# 1_3.net
KiCad netlist of a schematic drawn in Altium Designer
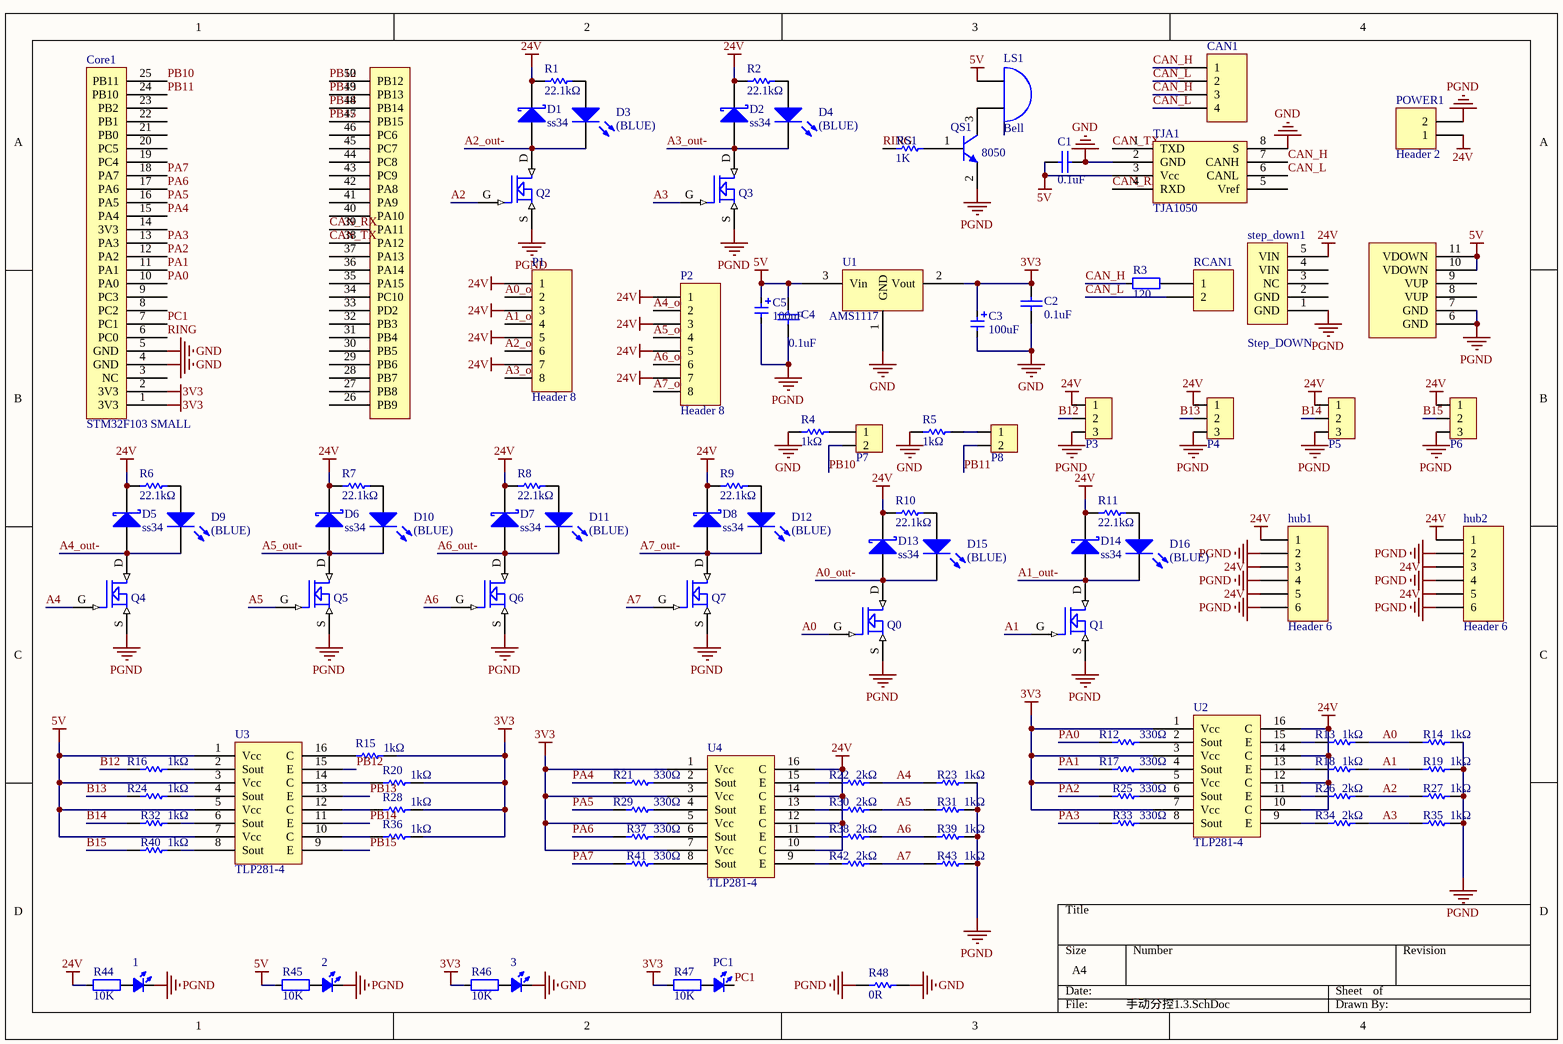
[diagram p0: 手动分控1.3.SchDoc]

(export (version "E")
  (design (tool "Eeschema 10.0.6"))
  (components
    (comp (ref "1")
      (value "LED_0603")
      (footprint "LED_0805_GREEN")
      (description "LED")
      (libsource (lib "Integrated_Library") (part "LED_0603"))
    )
    (comp (ref "2")
      (value "LED_0603")
      (footprint "LED_0805_GREEN")
      (description "LED")
      (libsource (lib "Integrated_Library") (part "LED_0603"))
    )
    (comp (ref "3")
      (value "LED_0603")
      (footprint "LED_0805_GREEN")
      (description "LED")
      (libsource (lib "Integrated_Library") (part "LED_0603"))
    )
    (comp (ref "C1")
      (value "0.1uF")
      (footprint "CAP-MLCC-0603")
      (description "Capacitor")
      (fields (field (name "Comment") "Cap") (field (name "PUBLISHER") "Altium Limited"))
      (libsource (lib "K60-mainboard-v3.1") (part "Cap"))
    )
    (comp (ref "C2")
      (value "0.1uF")
      (footprint "CAP-MLCC-0603")
      (description "Capacitor")
      (fields (field (name "Comment") "Cap") (field (name "PUBLISHER") "Altium Limited"))
      (libsource (lib "K60-mainboard-v3.1") (part "Cap"))
    )
    (comp (ref "C3")
      (value "100uF")
      (footprint "CAP-TAN-7343/CAPD")
      (description "Capacitor")
      (fields (field (name "Comment") "Cap_Tan_0805"))
      (libsource (lib "Integrated_Library") (part "Cap_Tan_0805"))
    )
    (comp (ref "C4")
      (value "0.1uF")
      (footprint "CAP-MLCC-0603")
      (description "Capacitor")
      (fields (field (name "Comment") "Cap") (field (name "PUBLISHER") "Altium Limited"))
      (libsource (lib "K60-mainboard-v3.1") (part "Cap"))
    )
    (comp (ref "C5")
      (value "100uF")
      (footprint "CAP-TAN-7343/CAPD")
      (description "Capacitor")
      (fields (field (name "Comment") "Cap_Tan_0805"))
      (libsource (lib "Integrated_Library") (part "Cap_Tan_0805"))
    )
    (comp (ref "CAN1")
      (value "Header 4")
      (footprint "Green_4P")
      (description "Header, 4-Pin")
      (fields (field (name "PUBLISHER") "Altium Limited"))
      (libsource (lib "Libraries_2014_0618") (part "Header 4"))
    )
    (comp (ref "Core1")
      (value "STM32F103 SMALL")
      (footprint "STM32F103Small")
      (libsource (lib "K60-mainboard-v3.1") (part "STM32F103 SMALL"))
    )
    (comp (ref "D1")
      (value "ss34")
      (footprint "ss34")
      (description "肖特基二极管")
      (fields (field (name "PUBLISHER") "Altium Limited"))
      (libsource (lib "Libraries_2014_0618") (part "DIODE-Schottky"))
    )
    (comp (ref "D2")
      (value "ss34")
      (footprint "ss34")
      (description "肖特基二极管")
      (fields (field (name "PUBLISHER") "Altium Limited"))
      (libsource (lib "Libraries_2014_0618") (part "DIODE-Schottky"))
    )
    (comp (ref "D3")
      (value "(BLUE)")
      (footprint "LED-0805")
      (description "LED")
      (fields (field (name "PUBLISHER") "Altium Limited"))
      (libsource (lib "Libraries_2014_0618") (part "LED"))
    )
    (comp (ref "D4")
      (value "(BLUE)")
      (footprint "LED-0805")
      (description "LED")
      (fields (field (name "PUBLISHER") "Altium Limited"))
      (libsource (lib "Libraries_2014_0618") (part "LED"))
    )
    (comp (ref "D5")
      (value "ss34")
      (footprint "ss34")
      (description "肖特基二极管")
      (fields (field (name "PUBLISHER") "Altium Limited"))
      (libsource (lib "Libraries_2014_0618") (part "DIODE-Schottky"))
    )
    (comp (ref "D6")
      (value "ss34")
      (footprint "ss34")
      (description "肖特基二极管")
      (fields (field (name "PUBLISHER") "Altium Limited"))
      (libsource (lib "Libraries_2014_0618") (part "DIODE-Schottky"))
    )
    (comp (ref "D7")
      (value "ss34")
      (footprint "ss34")
      (description "肖特基二极管")
      (fields (field (name "PUBLISHER") "Altium Limited"))
      (libsource (lib "Libraries_2014_0618") (part "DIODE-Schottky"))
    )
    (comp (ref "D8")
      (value "ss34")
      (footprint "ss34")
      (description "肖特基二极管")
      (fields (field (name "PUBLISHER") "Altium Limited"))
      (libsource (lib "Libraries_2014_0618") (part "DIODE-Schottky"))
    )
    (comp (ref "D9")
      (value "(BLUE)")
      (footprint "LED-0805")
      (description "LED")
      (fields (field (name "PUBLISHER") "Altium Limited"))
      (libsource (lib "Libraries_2014_0618") (part "LED"))
    )
    (comp (ref "D10")
      (value "(BLUE)")
      (footprint "LED-0805")
      (description "LED")
      (fields (field (name "PUBLISHER") "Altium Limited"))
      (libsource (lib "Libraries_2014_0618") (part "LED"))
    )
    (comp (ref "D11")
      (value "(BLUE)")
      (footprint "LED-0805")
      (description "LED")
      (fields (field (name "PUBLISHER") "Altium Limited"))
      (libsource (lib "Libraries_2014_0618") (part "LED"))
    )
    (comp (ref "D12")
      (value "(BLUE)")
      (footprint "LED-0805")
      (description "LED")
      (fields (field (name "PUBLISHER") "Altium Limited"))
      (libsource (lib "Libraries_2014_0618") (part "LED"))
    )
    (comp (ref "D13")
      (value "ss34")
      (footprint "ss34")
      (description "肖特基二极管")
      (fields (field (name "PUBLISHER") "Altium Limited"))
      (libsource (lib "Libraries_2014_0618") (part "DIODE-Schottky"))
    )
    (comp (ref "D14")
      (value "ss34")
      (footprint "ss34")
      (description "肖特基二极管")
      (fields (field (name "PUBLISHER") "Altium Limited"))
      (libsource (lib "Libraries_2014_0618") (part "DIODE-Schottky"))
    )
    (comp (ref "D15")
      (value "(BLUE)")
      (footprint "LED-0805")
      (description "LED")
      (fields (field (name "PUBLISHER") "Altium Limited"))
      (libsource (lib "Libraries_2014_0618") (part "LED"))
    )
    (comp (ref "D16")
      (value "(BLUE)")
      (footprint "LED-0805")
      (description "LED")
      (fields (field (name "PUBLISHER") "Altium Limited"))
      (libsource (lib "Libraries_2014_0618") (part "LED"))
    )
    (comp (ref "hub1")
      (value "Header 6")
      (footprint "Green_6P")
      (description "Header, 6-Pin")
      (fields (field (name "PUBLISHER") "Altium Limited"))
      (libsource (lib "Libraries_2014_0618") (part "Header 6"))
    )
    (comp (ref "hub2")
      (value "Header 6")
      (footprint "Green_6P")
      (description "Header, 6-Pin")
      (fields (field (name "PUBLISHER") "Altium Limited"))
      (libsource (lib "Libraries_2014_0618") (part "Header 6"))
    )
    (comp (ref "LS1")
      (value "Bell")
      (footprint "CAP-ELE-PIN200/DIA250")
      (description "Electrical Bell")
      (fields (field (name "PUBLISHER") "Altium Limited"))
      (libsource (lib "Miscellaneous Devices") (part "Bell"))
    )
    (comp (ref "P1")
      (value "Header 8")
      (footprint "Green_8P")
      (description "Header, 8-Pin")
      (fields (field (name "PUBLISHER") "Altium Limited"))
      (libsource (lib "K60-mainboard-v3.1") (part "Header 8"))
    )
    (comp (ref "P2")
      (value "Header 8")
      (footprint "Green_8P")
      (description "Header, 8-Pin")
      (fields (field (name "PUBLISHER") "Altium Limited"))
      (libsource (lib "K60-mainboard-v3.1") (part "Header 8"))
    )
    (comp (ref "P3")
      (value "HDR1x3_2.54")
      (footprint "Green_3P")
      (description "Header")
      (libsource (lib "Integrated_Library") (part "HDR1x3_2.54"))
    )
    (comp (ref "P4")
      (value "HDR1x3_2.54")
      (footprint "Green_3P")
      (description "Header")
      (libsource (lib "Integrated_Library") (part "HDR1x3_2.54"))
    )
    (comp (ref "P5")
      (value "HDR1x3_2.54")
      (footprint "Green_3P")
      (description "Header")
      (libsource (lib "Integrated_Library") (part "HDR1x3_2.54"))
    )
    (comp (ref "P6")
      (value "HDR1x3_2.54")
      (footprint "Green_3P")
      (description "Header")
      (libsource (lib "Integrated_Library") (part "HDR1x3_2.54"))
    )
    (comp (ref "P7")
      (value "HDR1x2_2.54")
      (footprint "Green_2P")
      (description "Header")
      (libsource (lib "Integrated_Library") (part "HDR1x2_2.54"))
    )
    (comp (ref "P8")
      (value "HDR1x2_2.54")
      (footprint "Green_2P")
      (description "Header")
      (libsource (lib "Integrated_Library") (part "HDR1x2_2.54"))
    )
    (comp (ref "PC1")
      (value "LED_0603")
      (footprint "LED_0805_GREEN")
      (description "LED")
      (libsource (lib "Integrated_Library") (part "LED_0603"))
    )
    (comp (ref "POWER1")
      (value "Header 2")
      (footprint "Green_2P")
      (description "Header, 2-Pin")
      (fields (field (name "PUBLISHER") "Altium Limited"))
      (libsource (lib "K60-mainboard-v3.1") (part "Header 2"))
    )
    (comp (ref "Q0")
      (value "MOSFET N")
      (footprint "LR7843")
      (description "IRF530")
      (libsource (lib "K60-mainboard-v3.1") (part "MOSFET N"))
    )
    (comp (ref "Q1")
      (value "MOSFET N")
      (footprint "LR7843")
      (description "IRF530")
      (libsource (lib "K60-mainboard-v3.1") (part "MOSFET N"))
    )
    (comp (ref "Q2")
      (value "MOSFET N")
      (footprint "NMOS_SOT23")
      (description "IRF530")
      (libsource (lib "K60-mainboard-v3.1") (part "MOSFET N"))
    )
    (comp (ref "Q3")
      (value "MOSFET N")
      (footprint "NMOS_SOT23")
      (description "IRF530")
      (libsource (lib "K60-mainboard-v3.1") (part "MOSFET N"))
    )
    (comp (ref "Q4")
      (value "MOSFET N")
      (footprint "NMOS_SOT23")
      (description "IRF530")
      (libsource (lib "K60-mainboard-v3.1") (part "MOSFET N"))
    )
    (comp (ref "Q5")
      (value "MOSFET N")
      (footprint "NMOS_SOT23")
      (description "IRF530")
      (libsource (lib "K60-mainboard-v3.1") (part "MOSFET N"))
    )
    (comp (ref "Q6")
      (value "MOSFET N")
      (footprint "NMOS_SOT23")
      (description "IRF530")
      (libsource (lib "K60-mainboard-v3.1") (part "MOSFET N"))
    )
    (comp (ref "Q7")
      (value "MOSFET N")
      (footprint "NMOS_SOT23")
      (description "IRF530")
      (libsource (lib "K60-mainboard-v3.1") (part "MOSFET N"))
    )
    (comp (ref "QS1")
      (value "8050")
      (footprint "SOT-23B_N")
      (description "NPN Bipolar Transistor")
      (fields (field (name "PUBLISHER") "Altium Limited"))
      (libsource (lib "附加元件") (part "QNPN"))
    )
    (comp (ref "R1")
      (value "22.1kΩ")
      (footprint "RES-0603")
      (description "电阻")
      (fields (field (name "PUBLISHER") "Altium Limited"))
      (libsource (lib "Libraries_2014_0618") (part "RES"))
    )
    (comp (ref "R2")
      (value "22.1kΩ")
      (footprint "RES-0603")
      (description "电阻")
      (fields (field (name "PUBLISHER") "Altium Limited"))
      (libsource (lib "Libraries_2014_0618") (part "RES"))
    )
    (comp (ref "R3")
      (value "120")
      (footprint "RES-0603")
      (description "Resistor")
      (fields (field (name "Comment") "Res_0603"))
      (libsource (lib "Integrated_Library") (part "Res_0603"))
    )
    (comp (ref "R4")
      (value "1kΩ")
      (footprint "RES-0603")
      (description "电阻")
      (fields (field (name "PUBLISHER") "Altium Limited"))
      (libsource (lib "Libraries_2014_0618") (part "RES"))
    )
    (comp (ref "R5")
      (value "1kΩ")
      (footprint "RES-0603")
      (description "电阻")
      (fields (field (name "PUBLISHER") "Altium Limited"))
      (libsource (lib "Libraries_2014_0618") (part "RES"))
    )
    (comp (ref "R6")
      (value "22.1kΩ")
      (footprint "RES-0603")
      (description "电阻")
      (fields (field (name "PUBLISHER") "Altium Limited"))
      (libsource (lib "Libraries_2014_0618") (part "RES"))
    )
    (comp (ref "R7")
      (value "22.1kΩ")
      (footprint "RES-0603")
      (description "电阻")
      (fields (field (name "PUBLISHER") "Altium Limited"))
      (libsource (lib "Libraries_2014_0618") (part "RES"))
    )
    (comp (ref "R8")
      (value "22.1kΩ")
      (footprint "RES-0603")
      (description "电阻")
      (fields (field (name "PUBLISHER") "Altium Limited"))
      (libsource (lib "Libraries_2014_0618") (part "RES"))
    )
    (comp (ref "R9")
      (value "22.1kΩ")
      (footprint "RES-0603")
      (description "电阻")
      (fields (field (name "PUBLISHER") "Altium Limited"))
      (libsource (lib "Libraries_2014_0618") (part "RES"))
    )
    (comp (ref "R10")
      (value "22.1kΩ")
      (footprint "RES-0603")
      (description "电阻")
      (fields (field (name "PUBLISHER") "Altium Limited"))
      (libsource (lib "Libraries_2014_0618") (part "RES"))
    )
    (comp (ref "R11")
      (value "22.1kΩ")
      (footprint "RES-0603")
      (description "电阻")
      (fields (field (name "PUBLISHER") "Altium Limited"))
      (libsource (lib "Libraries_2014_0618") (part "RES"))
    )
    (comp (ref "R12")
      (value "330Ω")
      (footprint "RES-0603")
      (description "电阻")
      (fields (field (name "Comment") "RES") (field (name "PUBLISHER") "Altium Limited"))
      (libsource (lib "Libraries_2014_0215") (part "RES"))
    )
    (comp (ref "R13")
      (value "1kΩ")
      (footprint "RES-0603")
      (description "电阻")
      (fields (field (name "PUBLISHER") "Altium Limited"))
      (libsource (lib "Libraries_2014_0618") (part "RES"))
    )
    (comp (ref "R14")
      (value "1kΩ")
      (footprint "RES-0603")
      (description "电阻")
      (fields (field (name "PUBLISHER") "Altium Limited"))
      (libsource (lib "Libraries_2014_0618") (part "RES"))
    )
    (comp (ref "R15")
      (value "1kΩ")
      (footprint "RES-0603")
      (description "电阻")
      (fields (field (name "Comment") "RES") (field (name "PUBLISHER") "Altium Limited"))
      (libsource (lib "Libraries_2014_0215") (part "RES"))
    )
    (comp (ref "R16")
      (value "1kΩ")
      (footprint "RES-0603")
      (description "电阻")
      (fields (field (name "Comment") "RES") (field (name "PUBLISHER") "Altium Limited"))
      (libsource (lib "Libraries_2014_0215") (part "RES"))
    )
    (comp (ref "R17")
      (value "330Ω")
      (footprint "RES-0603")
      (description "电阻")
      (fields (field (name "Comment") "RES") (field (name "PUBLISHER") "Altium Limited"))
      (libsource (lib "Libraries_2014_0215") (part "RES"))
    )
    (comp (ref "R18")
      (value "1kΩ")
      (footprint "RES-0603")
      (description "电阻")
      (fields (field (name "PUBLISHER") "Altium Limited"))
      (libsource (lib "Libraries_2014_0618") (part "RES"))
    )
    (comp (ref "R19")
      (value "1kΩ")
      (footprint "RES-0603")
      (description "电阻")
      (fields (field (name "PUBLISHER") "Altium Limited"))
      (libsource (lib "Libraries_2014_0618") (part "RES"))
    )
    (comp (ref "R20")
      (value "1kΩ")
      (footprint "RES-0603")
      (description "电阻")
      (fields (field (name "Comment") "RES") (field (name "PUBLISHER") "Altium Limited"))
      (libsource (lib "Libraries_2014_0215") (part "RES"))
    )
    (comp (ref "R21")
      (value "330Ω")
      (footprint "RES-0603")
      (description "电阻")
      (fields (field (name "Comment") "RES") (field (name "PUBLISHER") "Altium Limited"))
      (libsource (lib "Libraries_2014_0215") (part "RES"))
    )
    (comp (ref "R22")
      (value "2kΩ")
      (footprint "RES-0603")
      (description "电阻")
      (fields (field (name "PUBLISHER") "Altium Limited"))
      (libsource (lib "Libraries_2014_0618") (part "RES"))
    )
    (comp (ref "R23")
      (value "1kΩ")
      (footprint "RES-0603")
      (description "电阻")
      (fields (field (name "PUBLISHER") "Altium Limited"))
      (libsource (lib "Libraries_2014_0618") (part "RES"))
    )
    (comp (ref "R24")
      (value "1kΩ")
      (footprint "RES-0603")
      (description "电阻")
      (fields (field (name "Comment") "RES") (field (name "PUBLISHER") "Altium Limited"))
      (libsource (lib "Libraries_2014_0215") (part "RES"))
    )
    (comp (ref "R25")
      (value "330Ω")
      (footprint "RES-0603")
      (description "电阻")
      (fields (field (name "PUBLISHER") "Altium Limited"))
      (libsource (lib "Libraries_2014_0618") (part "RES"))
    )
    (comp (ref "R26")
      (value "2kΩ")
      (footprint "RES-0603")
      (description "电阻")
      (fields (field (name "PUBLISHER") "Altium Limited"))
      (libsource (lib "Libraries_2014_0618") (part "RES"))
    )
    (comp (ref "R27")
      (value "1kΩ")
      (footprint "RES-0603")
      (description "电阻")
      (fields (field (name "PUBLISHER") "Altium Limited"))
      (libsource (lib "Libraries_2014_0618") (part "RES"))
    )
    (comp (ref "R28")
      (value "1kΩ")
      (footprint "RES-0603")
      (description "电阻")
      (fields (field (name "Comment") "RES") (field (name "PUBLISHER") "Altium Limited"))
      (libsource (lib "Libraries_2014_0215") (part "RES"))
    )
    (comp (ref "R29")
      (value "330Ω")
      (footprint "RES-0603")
      (description "电阻")
      (fields (field (name "Comment") "RES") (field (name "PUBLISHER") "Altium Limited"))
      (libsource (lib "Libraries_2014_0215") (part "RES"))
    )
    (comp (ref "R30")
      (value "2kΩ")
      (footprint "RES-0603")
      (description "电阻")
      (fields (field (name "PUBLISHER") "Altium Limited"))
      (libsource (lib "Libraries_2014_0618") (part "RES"))
    )
    (comp (ref "R31")
      (value "1kΩ")
      (footprint "RES-0603")
      (description "电阻")
      (fields (field (name "PUBLISHER") "Altium Limited"))
      (libsource (lib "Libraries_2014_0618") (part "RES"))
    )
    (comp (ref "R32")
      (value "1kΩ")
      (footprint "RES-0603")
      (description "电阻")
      (fields (field (name "PUBLISHER") "Altium Limited"))
      (libsource (lib "Libraries_2014_0618") (part "RES"))
    )
    (comp (ref "R33")
      (value "330Ω")
      (footprint "RES-0603")
      (description "电阻")
      (fields (field (name "PUBLISHER") "Altium Limited"))
      (libsource (lib "Libraries_2014_0618") (part "RES"))
    )
    (comp (ref "R34")
      (value "2kΩ")
      (footprint "RES-0603")
      (description "电阻")
      (fields (field (name "PUBLISHER") "Altium Limited"))
      (libsource (lib "Libraries_2014_0618") (part "RES"))
    )
    (comp (ref "R35")
      (value "1kΩ")
      (footprint "RES-0603")
      (description "电阻")
      (fields (field (name "PUBLISHER") "Altium Limited"))
      (libsource (lib "Libraries_2014_0618") (part "RES"))
    )
    (comp (ref "R36")
      (value "1kΩ")
      (footprint "RES-0603")
      (description "电阻")
      (fields (field (name "Comment") "RES") (field (name "PUBLISHER") "Altium Limited"))
      (libsource (lib "Libraries_2014_0215") (part "RES"))
    )
    (comp (ref "R37")
      (value "330Ω")
      (footprint "RES-0603")
      (description "电阻")
      (fields (field (name "PUBLISHER") "Altium Limited"))
      (libsource (lib "Libraries_2014_0618") (part "RES"))
    )
    (comp (ref "R38")
      (value "2kΩ")
      (footprint "RES-0603")
      (description "电阻")
      (fields (field (name "PUBLISHER") "Altium Limited"))
      (libsource (lib "Libraries_2014_0618") (part "RES"))
    )
    (comp (ref "R39")
      (value "1kΩ")
      (footprint "RES-0603")
      (description "电阻")
      (fields (field (name "PUBLISHER") "Altium Limited"))
      (libsource (lib "Libraries_2014_0618") (part "RES"))
    )
    (comp (ref "R40")
      (value "1kΩ")
      (footprint "RES-0603")
      (description "电阻")
      (fields (field (name "PUBLISHER") "Altium Limited"))
      (libsource (lib "Libraries_2014_0618") (part "RES"))
    )
    (comp (ref "R41")
      (value "330Ω")
      (footprint "RES-0603")
      (description "电阻")
      (fields (field (name "PUBLISHER") "Altium Limited"))
      (libsource (lib "Libraries_2014_0618") (part "RES"))
    )
    (comp (ref "R42")
      (value "2kΩ")
      (footprint "RES-0603")
      (description "电阻")
      (fields (field (name "PUBLISHER") "Altium Limited"))
      (libsource (lib "Libraries_2014_0618") (part "RES"))
    )
    (comp (ref "R43")
      (value "1kΩ")
      (footprint "RES-0603")
      (description "电阻")
      (fields (field (name "PUBLISHER") "Altium Limited"))
      (libsource (lib "Libraries_2014_0618") (part "RES"))
    )
    (comp (ref "R44")
      (value "10K")
      (footprint "RES-0603")
      (description "Resistor")
      (fields (field (name "Comment") "Res_0603"))
      (libsource (lib "Integrated_Library") (part "Res_0603"))
    )
    (comp (ref "R45")
      (value "10K")
      (footprint "RES-0603")
      (description "Resistor")
      (fields (field (name "Comment") "Res_0603"))
      (libsource (lib "Integrated_Library") (part "Res_0603"))
    )
    (comp (ref "R46")
      (value "10K")
      (footprint "RES-0603")
      (description "Resistor")
      (fields (field (name "Comment") "Res_0603"))
      (libsource (lib "Integrated_Library") (part "Res_0603"))
    )
    (comp (ref "R47")
      (value "10K")
      (footprint "RES-0603")
      (description "Resistor")
      (fields (field (name "Comment") "Res_0603"))
      (libsource (lib "Integrated_Library") (part "Res_0603"))
    )
    (comp (ref "R48")
      (value "0R")
      (footprint "RES-0603")
      (description "Resistor")
      (fields (field (name "Comment") "Res1") (field (name "PUBLISHER") "Altium Limited"))
      (libsource (lib "K60-mainboard-v3.1") (part "Res1"))
    )
    (comp (ref "RCAN1")
      (value "~")
      (footprint "HDR1X2")
      (description "Header, 2-Pin")
      (fields (field (name "PUBLISHER") "Altium Limited"))
      (libsource (lib "Miscellaneous Connectors") (part "Header 2"))
    )
    (comp (ref "RS1")
      (value "1K")
      (footprint "RES-0603")
      (description "Resistor")
      (fields (field (name "Comment") "Res1") (field (name "PUBLISHER") "Altium Limited"))
      (libsource (lib "K60-mainboard-v3.1") (part "Res1"))
    )
    (comp (ref "step_down1")
      (value "Step_DOWN")
      (footprint "Step_Up_Down")
      (libsource (lib "K60-mainboard-v3.1") (part "Step_DOWN"))
    )
    (comp (ref "TJA1")
      (value "TJA1050")
      (footprint "TJA1050")
      (description "CAN总线收发器")
      (libsource (lib "Libraries_2014_0618") (part "TJA1050"))
    )
    (comp (ref "U1") (value "AMS1117") (footprint "SOT223-3") (libsource (lib "AMS1117") (part "AMS１１１７")))
    (comp (ref "U2")
      (value "TLP281-4")
      (footprint "SOP16")
      (description "TLP521-4,TLP281-4")
      (libsource (lib "Libraries_2014_0215") (part "IC-TLP521-4"))
    )
    (comp (ref "U3")
      (value "TLP281-4")
      (footprint "SOP16")
      (description "TLP521-4,TLP281-4")
      (libsource (lib "Libraries_2014_0215") (part "IC-TLP521-4"))
    )
    (comp (ref "U4")
      (value "TLP281-4")
      (footprint "SOP16")
      (description "TLP521-4,TLP281-4")
      (libsource (lib "Libraries_2014_0215") (part "IC-TLP521-4"))
    )
  )
  (nets
    (net (code "1") (name "/A0") (class "Default")
      (node (ref "Q0") (pin "G") (pinfunction "G_G") (pintype "input"))
      (node (ref "R13") (pin "2") (pinfunction "2_2") (pintype "passive"))
      (node (ref "R14") (pin "2") (pinfunction "2_2") (pintype "passive"))
    )
    (net (code "2") (name "/A0_out-") (class "Default")
      (node (ref "D13") (pin "A") (pinfunction "A_A") (pintype "passive"))
      (node (ref "D15") (pin "2") (pinfunction "K_2") (pintype "passive"))
      (node (ref "P1") (pin "2") (pinfunction "2_2") (pintype "passive"))
      (node (ref "Q0") (pin "D") (pinfunction "D_D") (pintype "input"))
    )
    (net (code "3") (name "/A1") (class "Default")
      (node (ref "Q1") (pin "G") (pinfunction "G_G") (pintype "input"))
      (node (ref "R18") (pin "2") (pinfunction "2_2") (pintype "passive"))
      (node (ref "R19") (pin "2") (pinfunction "2_2") (pintype "passive"))
    )
    (net (code "4") (name "/A1_out-") (class "Default")
      (node (ref "D14") (pin "A") (pinfunction "A_A") (pintype "passive"))
      (node (ref "D16") (pin "2") (pinfunction "K_2") (pintype "passive"))
      (node (ref "P1") (pin "4") (pinfunction "4_4") (pintype "passive"))
      (node (ref "Q1") (pin "D") (pinfunction "D_D") (pintype "input"))
    )
    (net (code "5") (name "/A2") (class "Default")
      (node (ref "Q2") (pin "G") (pinfunction "G_G") (pintype "input"))
      (node (ref "R26") (pin "2") (pinfunction "2_2") (pintype "passive"))
      (node (ref "R27") (pin "2") (pinfunction "2_2") (pintype "passive"))
    )
    (net (code "6") (name "/A2_out-") (class "Default")
      (node (ref "D1") (pin "A") (pinfunction "A_A") (pintype "passive"))
      (node (ref "D3") (pin "2") (pinfunction "K_2") (pintype "passive"))
      (node (ref "P1") (pin "6") (pinfunction "6_6") (pintype "passive"))
      (node (ref "Q2") (pin "D") (pinfunction "D_D") (pintype "input"))
    )
    (net (code "7") (name "/A3") (class "Default")
      (node (ref "Q3") (pin "G") (pinfunction "G_G") (pintype "input"))
      (node (ref "R34") (pin "2") (pinfunction "2_2") (pintype "passive"))
      (node (ref "R35") (pin "2") (pinfunction "2_2") (pintype "passive"))
    )
    (net (code "8") (name "/A3_out-") (class "Default")
      (node (ref "D2") (pin "A") (pinfunction "A_A") (pintype "passive"))
      (node (ref "D4") (pin "2") (pinfunction "K_2") (pintype "passive"))
      (node (ref "P1") (pin "8") (pinfunction "8_8") (pintype "passive"))
      (node (ref "Q3") (pin "D") (pinfunction "D_D") (pintype "input"))
    )
    (net (code "9") (name "/A4") (class "Default")
      (node (ref "Q4") (pin "G") (pinfunction "G_G") (pintype "input"))
      (node (ref "R22") (pin "2") (pinfunction "2_2") (pintype "passive"))
      (node (ref "R23") (pin "2") (pinfunction "2_2") (pintype "passive"))
    )
    (net (code "10") (name "/A4_out-") (class "Default")
      (node (ref "D5") (pin "A") (pinfunction "A_A") (pintype "passive"))
      (node (ref "D9") (pin "2") (pinfunction "K_2") (pintype "passive"))
      (node (ref "P2") (pin "2") (pinfunction "2_2") (pintype "passive"))
      (node (ref "Q4") (pin "D") (pinfunction "D_D") (pintype "input"))
    )
    (net (code "11") (name "/A5") (class "Default")
      (node (ref "Q5") (pin "G") (pinfunction "G_G") (pintype "input"))
      (node (ref "R30") (pin "2") (pinfunction "2_2") (pintype "passive"))
      (node (ref "R31") (pin "2") (pinfunction "2_2") (pintype "passive"))
    )
    (net (code "12") (name "/A5_out-") (class "Default")
      (node (ref "D10") (pin "2") (pinfunction "K_2") (pintype "passive"))
      (node (ref "D6") (pin "A") (pinfunction "A_A") (pintype "passive"))
      (node (ref "P2") (pin "4") (pinfunction "4_4") (pintype "passive"))
      (node (ref "Q5") (pin "D") (pinfunction "D_D") (pintype "input"))
    )
    (net (code "13") (name "/A6") (class "Default")
      (node (ref "Q6") (pin "G") (pinfunction "G_G") (pintype "input"))
      (node (ref "R38") (pin "2") (pinfunction "2_2") (pintype "passive"))
      (node (ref "R39") (pin "2") (pinfunction "2_2") (pintype "passive"))
    )
    (net (code "14") (name "/A6_out-") (class "Default")
      (node (ref "D11") (pin "2") (pinfunction "K_2") (pintype "passive"))
      (node (ref "D7") (pin "A") (pinfunction "A_A") (pintype "passive"))
      (node (ref "P2") (pin "6") (pinfunction "6_6") (pintype "passive"))
      (node (ref "Q6") (pin "D") (pinfunction "D_D") (pintype "input"))
    )
    (net (code "15") (name "/A7") (class "Default")
      (node (ref "Q7") (pin "G") (pinfunction "G_G") (pintype "input"))
      (node (ref "R42") (pin "2") (pinfunction "2_2") (pintype "passive"))
      (node (ref "R43") (pin "2") (pinfunction "2_2") (pintype "passive"))
    )
    (net (code "16") (name "/A7_out-") (class "Default")
      (node (ref "D12") (pin "2") (pinfunction "K_2") (pintype "passive"))
      (node (ref "D8") (pin "A") (pinfunction "A_A") (pintype "passive"))
      (node (ref "P2") (pin "8") (pinfunction "8_8") (pintype "passive"))
      (node (ref "Q7") (pin "D") (pinfunction "D_D") (pintype "input"))
    )
    (net (code "17") (name "/B12") (class "Default")
      (node (ref "P3") (pin "2") (pinfunction "2_2") (pintype "passive"))
      (node (ref "R16") (pin "1") (pinfunction "1_1") (pintype "passive"))
    )
    (net (code "18") (name "/B13") (class "Default")
      (node (ref "P4") (pin "2") (pinfunction "2_2") (pintype "passive"))
      (node (ref "R24") (pin "1") (pinfunction "1_1") (pintype "passive"))
    )
    (net (code "19") (name "/B14") (class "Default")
      (node (ref "P5") (pin "2") (pinfunction "2_2") (pintype "passive"))
      (node (ref "R32") (pin "1") (pinfunction "1_1") (pintype "passive"))
    )
    (net (code "20") (name "/B15") (class "Default")
      (node (ref "P6") (pin "2") (pinfunction "2_2") (pintype "passive"))
      (node (ref "R40") (pin "1") (pinfunction "1_1") (pintype "passive"))
    )
    (net (code "21") (name "/CAN_H") (class "Default")
      (node (ref "CAN1") (pin "1") (pinfunction "1_1") (pintype "passive"))
      (node (ref "CAN1") (pin "3") (pinfunction "3_3") (pintype "passive"))
      (node (ref "R3") (pin "2") (pinfunction "2_2") (pintype "passive"))
      (node (ref "TJA1") (pin "7") (pinfunction "CANH_7") (pintype "passive"))
    )
    (net (code "22") (name "/CAN_L") (class "Default")
      (node (ref "CAN1") (pin "2") (pinfunction "2_2") (pintype "passive"))
      (node (ref "CAN1") (pin "4") (pinfunction "4_4") (pintype "passive"))
      (node (ref "RCAN1") (pin "2") (pinfunction "2_2") (pintype "passive"))
      (node (ref "TJA1") (pin "6") (pinfunction "CANL_6") (pintype "passive"))
    )
    (net (code "23") (name "/CAN_RX") (class "Default")
      (node (ref "Core1") (pin "39") (pinfunction "PA11_39") (pintype "passive"))
      (node (ref "TJA1") (pin "4") (pinfunction "RXD_4") (pintype "passive"))
    )
    (net (code "24") (name "/CAN_TX") (class "Default")
      (node (ref "Core1") (pin "38") (pinfunction "PA12_38") (pintype "passive"))
      (node (ref "TJA1") (pin "1") (pinfunction "TXD_1") (pintype "passive"))
    )
    (net (code "25") (name "/PA0") (class "Default")
      (node (ref "Core1") (pin "10") (pinfunction "PA0_10") (pintype "passive"))
      (node (ref "R12") (pin "1") (pinfunction "1_1") (pintype "passive"))
    )
    (net (code "26") (name "/PA1") (class "Default")
      (node (ref "Core1") (pin "11") (pinfunction "PA1_11") (pintype "passive"))
      (node (ref "R17") (pin "1") (pinfunction "1_1") (pintype "passive"))
    )
    (net (code "27") (name "/PA2") (class "Default")
      (node (ref "Core1") (pin "12") (pinfunction "PA2_12") (pintype "passive"))
      (node (ref "R25") (pin "1") (pinfunction "1_1") (pintype "passive"))
    )
    (net (code "28") (name "/PA3") (class "Default")
      (node (ref "Core1") (pin "13") (pinfunction "PA3_13") (pintype "passive"))
      (node (ref "R33") (pin "1") (pinfunction "1_1") (pintype "passive"))
    )
    (net (code "29") (name "/PA4") (class "Default")
      (node (ref "Core1") (pin "15") (pinfunction "PA4_15") (pintype "passive"))
      (node (ref "R21") (pin "1") (pinfunction "1_1") (pintype "passive"))
    )
    (net (code "30") (name "/PA5") (class "Default")
      (node (ref "Core1") (pin "16") (pinfunction "PA5_16") (pintype "passive"))
      (node (ref "R29") (pin "1") (pinfunction "1_1") (pintype "passive"))
    )
    (net (code "31") (name "/PA6") (class "Default")
      (node (ref "Core1") (pin "17") (pinfunction "PA6_17") (pintype "passive"))
      (node (ref "R37") (pin "1") (pinfunction "1_1") (pintype "passive"))
    )
    (net (code "32") (name "/PA7") (class "Default")
      (node (ref "Core1") (pin "18") (pinfunction "PA7_18") (pintype "passive"))
      (node (ref "R41") (pin "1") (pinfunction "1_1") (pintype "passive"))
    )
    (net (code "33") (name "/PB10") (class "Default")
      (node (ref "Core1") (pin "25") (pinfunction "PB11_25") (pintype "passive"))
      (node (ref "P7") (pin "2") (pinfunction "2_2") (pintype "passive"))
    )
    (net (code "34") (name "/PB11") (class "Default")
      (node (ref "Core1") (pin "24") (pinfunction "PB10_24") (pintype "passive"))
      (node (ref "P8") (pin "2") (pinfunction "2_2") (pintype "passive"))
    )
    (net (code "35") (name "/PB12") (class "Default")
      (node (ref "Core1") (pin "50") (pinfunction "PB12_50") (pintype "passive"))
      (node (ref "U3") (pin "15") (pinfunction "E_15") (pintype "power_in"))
    )
    (net (code "36") (name "/PB13") (class "Default")
      (node (ref "Core1") (pin "49") (pinfunction "PB13_49") (pintype "passive"))
      (node (ref "U3") (pin "13") (pinfunction "E_13") (pintype "power_in"))
    )
    (net (code "37") (name "/PB14") (class "Default")
      (node (ref "Core1") (pin "48") (pinfunction "PB14_48") (pintype "passive"))
      (node (ref "U3") (pin "11") (pinfunction "E_11") (pintype "power_in"))
    )
    (net (code "38") (name "/PB15") (class "Default")
      (node (ref "Core1") (pin "47") (pinfunction "PB15_47") (pintype "passive"))
      (node (ref "U3") (pin "9") (pinfunction "E_9") (pintype "power_in"))
    )
    (net (code "39") (name "/PC1") (class "Default")
      (node (ref "Core1") (pin "7") (pinfunction "PC1_7") (pintype "passive"))
      (node (ref "PC1") (pin "2") (pinfunction "K_2") (pintype "passive"))
    )
    (net (code "40") (name "/RING") (class "Default")
      (node (ref "Core1") (pin "6") (pinfunction "PC0_6") (pintype "passive"))
      (node (ref "RS1") (pin "2") (pinfunction "2_2") (pintype "passive"))
    )
    (net (code "41") (name "3V3") (class "Default")
      (node (ref "C2") (pin "2") (pinfunction "2_2") (pintype "passive"))
      (node (ref "C3") (pin "1") (pinfunction "1_1") (pintype "passive"))
      (node (ref "Core1") (pin "1") (pinfunction "3V3_1") (pintype "passive"))
      (node (ref "Core1") (pin "2") (pinfunction "3V3_2") (pintype "passive"))
      (node (ref "R15") (pin "2") (pinfunction "2_2") (pintype "passive"))
      (node (ref "R20") (pin "2") (pinfunction "2_2") (pintype "passive"))
      (node (ref "R28") (pin "2") (pinfunction "2_2") (pintype "passive"))
      (node (ref "R36") (pin "2") (pinfunction "2_2") (pintype "passive"))
      (node (ref "R46") (pin "2") (pinfunction "2_2") (pintype "passive"))
      (node (ref "R47") (pin "2") (pinfunction "2_2") (pintype "passive"))
      (node (ref "U1") (pin "2") (pinfunction "Vout_2") (pintype "passive"))
      (node (ref "U2") (pin "1") (pinfunction "Vcc_1") (pintype "power_in"))
      (node (ref "U2") (pin "3") (pinfunction "Vcc_3") (pintype "power_in"))
      (node (ref "U2") (pin "5") (pinfunction "Vcc_5") (pintype "power_in"))
      (node (ref "U2") (pin "7") (pinfunction "Vcc_7") (pintype "power_in"))
      (node (ref "U4") (pin "1") (pinfunction "Vcc_1") (pintype "power_in"))
      (node (ref "U4") (pin "3") (pinfunction "Vcc_3") (pintype "power_in"))
      (node (ref "U4") (pin "5") (pinfunction "Vcc_5") (pintype "power_in"))
      (node (ref "U4") (pin "7") (pinfunction "Vcc_7") (pintype "power_in"))
    )
    (net (code "42") (name "5V") (class "Default")
      (node (ref "C1") (pin "1") (pinfunction "1_1") (pintype "passive"))
      (node (ref "C4") (pin "2") (pinfunction "2_2") (pintype "passive"))
      (node (ref "C5") (pin "1") (pinfunction "1_1") (pintype "passive"))
      (node (ref "LS1") (pin "1") (pinfunction "A_1") (pintype "passive"))
      (node (ref "R45") (pin "2") (pinfunction "2_2") (pintype "passive"))
      (node (ref "TJA1") (pin "3") (pinfunction "Vcc_3") (pintype "passive"))
      (node (ref "U1") (pin "3") (pinfunction "Vin_3") (pintype "passive"))
      (node (ref "U3") (pin "1") (pinfunction "Vcc_1") (pintype "power_in"))
      (node (ref "U3") (pin "3") (pinfunction "Vcc_3") (pintype "power_in"))
      (node (ref "U3") (pin "5") (pinfunction "Vcc_5") (pintype "power_in"))
      (node (ref "U3") (pin "7") (pinfunction "Vcc_7") (pintype "power_in"))
      (node (ref "step_down1") (pin "10") (pinfunction "VDOWN_10") (pintype "passive"))
      (node (ref "step_down1") (pin "11") (pinfunction "VDOWN_11") (pintype "passive"))
    )
    (net (code "43") (name "24V") (class "Default")
      (node (ref "D1") (pin "K") (pinfunction "K_K") (pintype "passive"))
      (node (ref "D13") (pin "K") (pinfunction "K_K") (pintype "passive"))
      (node (ref "D14") (pin "K") (pinfunction "K_K") (pintype "passive"))
      (node (ref "D2") (pin "K") (pinfunction "K_K") (pintype "passive"))
      (node (ref "D5") (pin "K") (pinfunction "K_K") (pintype "passive"))
      (node (ref "D6") (pin "K") (pinfunction "K_K") (pintype "passive"))
      (node (ref "D7") (pin "K") (pinfunction "K_K") (pintype "passive"))
      (node (ref "D8") (pin "K") (pinfunction "K_K") (pintype "passive"))
      (node (ref "P1") (pin "1") (pinfunction "1_1") (pintype "passive"))
      (node (ref "P1") (pin "3") (pinfunction "3_3") (pintype "passive"))
      (node (ref "P1") (pin "5") (pinfunction "5_5") (pintype "passive"))
      (node (ref "P1") (pin "7") (pinfunction "7_7") (pintype "passive"))
      (node (ref "P2") (pin "1") (pinfunction "1_1") (pintype "passive"))
      (node (ref "P2") (pin "3") (pinfunction "3_3") (pintype "passive"))
      (node (ref "P2") (pin "5") (pinfunction "5_5") (pintype "passive"))
      (node (ref "P2") (pin "7") (pinfunction "7_7") (pintype "passive"))
      (node (ref "P3") (pin "1") (pinfunction "1_1") (pintype "passive"))
      (node (ref "P4") (pin "1") (pinfunction "1_1") (pintype "passive"))
      (node (ref "P5") (pin "1") (pinfunction "1_1") (pintype "passive"))
      (node (ref "P6") (pin "1") (pinfunction "1_1") (pintype "passive"))
      (node (ref "POWER1") (pin "1") (pinfunction "1_1") (pintype "passive"))
      (node (ref "R1") (pin "2") (pinfunction "2_2") (pintype "passive"))
      (node (ref "R10") (pin "2") (pinfunction "2_2") (pintype "passive"))
      (node (ref "R11") (pin "1") (pinfunction "1_1") (pintype "passive"))
      (node (ref "R2") (pin "1") (pinfunction "1_1") (pintype "passive"))
      (node (ref "R44") (pin "2") (pinfunction "2_2") (pintype "passive"))
      (node (ref "R6") (pin "2") (pinfunction "2_2") (pintype "passive"))
      (node (ref "R7") (pin "1") (pinfunction "1_1") (pintype "passive"))
      (node (ref "R8") (pin "2") (pinfunction "2_2") (pintype "passive"))
      (node (ref "R9") (pin "1") (pinfunction "1_1") (pintype "passive"))
      (node (ref "U2") (pin "10") (pinfunction "C_10") (pintype "power_in"))
      (node (ref "U2") (pin "12") (pinfunction "C_12") (pintype "power_in"))
      (node (ref "U2") (pin "14") (pinfunction "C_14") (pintype "power_in"))
      (node (ref "U2") (pin "16") (pinfunction "C_16") (pintype "power_in"))
      (node (ref "U4") (pin "10") (pinfunction "C_10") (pintype "power_in"))
      (node (ref "U4") (pin "12") (pinfunction "C_12") (pintype "power_in"))
      (node (ref "U4") (pin "14") (pinfunction "C_14") (pintype "power_in"))
      (node (ref "U4") (pin "16") (pinfunction "C_16") (pintype "power_in"))
      (node (ref "hub1") (pin "1") (pinfunction "1_1") (pintype "passive"))
      (node (ref "hub1") (pin "3") (pinfunction "3_3") (pintype "passive"))
      (node (ref "hub1") (pin "5") (pinfunction "5_5") (pintype "passive"))
      (node (ref "hub2") (pin "1") (pinfunction "1_1") (pintype "passive"))
      (node (ref "hub2") (pin "3") (pinfunction "3_3") (pintype "passive"))
      (node (ref "hub2") (pin "5") (pinfunction "5_5") (pintype "passive"))
      (node (ref "step_down1") (pin "5") (pinfunction "VIN_5") (pintype "passive"))
    )
    (net (code "44") (name "GND") (class "Default")
      (node (ref "3") (pin "2") (pinfunction "K_2") (pintype "passive"))
      (node (ref "C1") (pin "2") (pinfunction "2_2") (pintype "passive"))
      (node (ref "C2") (pin "1") (pinfunction "1_1") (pintype "passive"))
      (node (ref "C3") (pin "2") (pinfunction "2_2") (pintype "passive"))
      (node (ref "Core1") (pin "4") (pinfunction "GND_4") (pintype "passive"))
      (node (ref "Core1") (pin "5") (pinfunction "GND_5") (pintype "passive"))
      (node (ref "R4") (pin "1") (pinfunction "1_1") (pintype "passive"))
      (node (ref "R48") (pin "1") (pinfunction "1_1") (pintype "passive"))
      (node (ref "R5") (pin "1") (pinfunction "1_1") (pintype "passive"))
      (node (ref "TJA1") (pin "2") (pinfunction "GND_2") (pintype "passive"))
      (node (ref "TJA1") (pin "8") (pinfunction "S_8") (pintype "passive"))
      (node (ref "U1") (pin "1") (pinfunction "GND_1") (pintype "passive"))
    )
    (net (code "45") (name "Net-(1-A)") (class "Default")
      (node (ref "1") (pin "1") (pinfunction "A_1") (pintype "passive"))
      (node (ref "R44") (pin "1") (pinfunction "1_1") (pintype "passive"))
    )
    (net (code "46") (name "Net-(2-A)") (class "Default")
      (node (ref "2") (pin "1") (pinfunction "A_1") (pintype "passive"))
      (node (ref "R45") (pin "1") (pinfunction "1_1") (pintype "passive"))
    )
    (net (code "47") (name "Net-(3-A)") (class "Default")
      (node (ref "3") (pin "1") (pinfunction "A_1") (pintype "passive"))
      (node (ref "R46") (pin "1") (pinfunction "1_1") (pintype "passive"))
    )
    (net (code "48") (name "Net-(D3-A)") (class "Default")
      (node (ref "D3") (pin "1") (pinfunction "A_1") (pintype "passive"))
      (node (ref "R1") (pin "1") (pinfunction "1_1") (pintype "passive"))
    )
    (net (code "49") (name "Net-(D4-A)") (class "Default")
      (node (ref "D4") (pin "1") (pinfunction "A_1") (pintype "passive"))
      (node (ref "R2") (pin "2") (pinfunction "2_2") (pintype "passive"))
    )
    (net (code "50") (name "Net-(D9-A)") (class "Default")
      (node (ref "D9") (pin "1") (pinfunction "A_1") (pintype "passive"))
      (node (ref "R6") (pin "1") (pinfunction "1_1") (pintype "passive"))
    )
    (net (code "51") (name "Net-(D10-A)") (class "Default")
      (node (ref "D10") (pin "1") (pinfunction "A_1") (pintype "passive"))
      (node (ref "R7") (pin "2") (pinfunction "2_2") (pintype "passive"))
    )
    (net (code "52") (name "Net-(D11-A)") (class "Default")
      (node (ref "D11") (pin "1") (pinfunction "A_1") (pintype "passive"))
      (node (ref "R8") (pin "1") (pinfunction "1_1") (pintype "passive"))
    )
    (net (code "53") (name "Net-(D12-A)") (class "Default")
      (node (ref "D12") (pin "1") (pinfunction "A_1") (pintype "passive"))
      (node (ref "R9") (pin "2") (pinfunction "2_2") (pintype "passive"))
    )
    (net (code "54") (name "Net-(D15-A)") (class "Default")
      (node (ref "D15") (pin "1") (pinfunction "A_1") (pintype "passive"))
      (node (ref "R10") (pin "1") (pinfunction "1_1") (pintype "passive"))
    )
    (net (code "55") (name "Net-(D16-A)") (class "Default")
      (node (ref "D16") (pin "1") (pinfunction "A_1") (pintype "passive"))
      (node (ref "R11") (pin "2") (pinfunction "2_2") (pintype "passive"))
    )
    (net (code "56") (name "Net-(LS1-B)") (class "Default")
      (node (ref "LS1") (pin "2") (pinfunction "B_2") (pintype "passive"))
      (node (ref "QS1") (pin "3") (pinfunction "C_3") (pintype "passive"))
    )
    (net (code "57") (name "Net-(P7-Pad1)") (class "Default")
      (node (ref "P7") (pin "1") (pinfunction "1_1") (pintype "passive"))
      (node (ref "R4") (pin "2") (pinfunction "2_2") (pintype "passive"))
    )
    (net (code "58") (name "Net-(P8-Pad1)") (class "Default")
      (node (ref "P8") (pin "1") (pinfunction "1_1") (pintype "passive"))
      (node (ref "R5") (pin "2") (pinfunction "2_2") (pintype "passive"))
    )
    (net (code "59") (name "Net-(PC1-A)") (class "Default")
      (node (ref "PC1") (pin "1") (pinfunction "A_1") (pintype "passive"))
      (node (ref "R47") (pin "1") (pinfunction "1_1") (pintype "passive"))
    )
    (net (code "60") (name "Net-(QS1-B)") (class "Default")
      (node (ref "QS1") (pin "1") (pinfunction "B_1") (pintype "passive"))
      (node (ref "RS1") (pin "1") (pinfunction "1_1") (pintype "passive"))
    )
    (net (code "61") (name "Net-(R3-Pad1)") (class "Default")
      (node (ref "R3") (pin "1") (pinfunction "1_1") (pintype "passive"))
      (node (ref "RCAN1") (pin "1") (pinfunction "1_1") (pintype "passive"))
    )
    (net (code "62") (name "Net-(R12-Pad2)") (class "Default")
      (node (ref "R12") (pin "2") (pinfunction "2_2") (pintype "passive"))
      (node (ref "U2") (pin "2") (pinfunction "Sout_2") (pintype "power_in"))
    )
    (net (code "63") (name "Net-(R13-Pad1)") (class "Default")
      (node (ref "R13") (pin "1") (pinfunction "1_1") (pintype "passive"))
      (node (ref "U2") (pin "15") (pinfunction "E_15") (pintype "power_in"))
    )
    (net (code "64") (name "Net-(R15-Pad1)") (class "Default")
      (node (ref "R15") (pin "1") (pinfunction "1_1") (pintype "passive"))
      (node (ref "U3") (pin "16") (pinfunction "C_16") (pintype "power_in"))
    )
    (net (code "65") (name "Net-(R16-Pad2)") (class "Default")
      (node (ref "R16") (pin "2") (pinfunction "2_2") (pintype "passive"))
      (node (ref "U3") (pin "2") (pinfunction "Sout_2") (pintype "power_in"))
    )
    (net (code "66") (name "Net-(R17-Pad2)") (class "Default")
      (node (ref "R17") (pin "2") (pinfunction "2_2") (pintype "passive"))
      (node (ref "U2") (pin "4") (pinfunction "Sout_4") (pintype "power_in"))
    )
    (net (code "67") (name "Net-(R18-Pad1)") (class "Default")
      (node (ref "R18") (pin "1") (pinfunction "1_1") (pintype "passive"))
      (node (ref "U2") (pin "13") (pinfunction "E_13") (pintype "power_in"))
    )
    (net (code "68") (name "Net-(R20-Pad1)") (class "Default")
      (node (ref "R20") (pin "1") (pinfunction "1_1") (pintype "passive"))
      (node (ref "U3") (pin "14") (pinfunction "C_14") (pintype "power_in"))
    )
    (net (code "69") (name "Net-(R21-Pad2)") (class "Default")
      (node (ref "R21") (pin "2") (pinfunction "2_2") (pintype "passive"))
      (node (ref "U4") (pin "2") (pinfunction "Sout_2") (pintype "power_in"))
    )
    (net (code "70") (name "Net-(R22-Pad1)") (class "Default")
      (node (ref "R22") (pin "1") (pinfunction "1_1") (pintype "passive"))
      (node (ref "U4") (pin "15") (pinfunction "E_15") (pintype "power_in"))
    )
    (net (code "71") (name "Net-(R24-Pad2)") (class "Default")
      (node (ref "R24") (pin "2") (pinfunction "2_2") (pintype "passive"))
      (node (ref "U3") (pin "4") (pinfunction "Sout_4") (pintype "power_in"))
    )
    (net (code "72") (name "Net-(R25-Pad2)") (class "Default")
      (node (ref "R25") (pin "2") (pinfunction "2_2") (pintype "passive"))
      (node (ref "U2") (pin "6") (pinfunction "Sout_6") (pintype "power_in"))
    )
    (net (code "73") (name "Net-(R26-Pad1)") (class "Default")
      (node (ref "R26") (pin "1") (pinfunction "1_1") (pintype "passive"))
      (node (ref "U2") (pin "11") (pinfunction "E_11") (pintype "power_in"))
    )
    (net (code "74") (name "Net-(R28-Pad1)") (class "Default")
      (node (ref "R28") (pin "1") (pinfunction "1_1") (pintype "passive"))
      (node (ref "U3") (pin "12") (pinfunction "C_12") (pintype "power_in"))
    )
    (net (code "75") (name "Net-(R29-Pad2)") (class "Default")
      (node (ref "R29") (pin "2") (pinfunction "2_2") (pintype "passive"))
      (node (ref "U4") (pin "4") (pinfunction "Sout_4") (pintype "power_in"))
    )
    (net (code "76") (name "Net-(R30-Pad1)") (class "Default")
      (node (ref "R30") (pin "1") (pinfunction "1_1") (pintype "passive"))
      (node (ref "U4") (pin "13") (pinfunction "E_13") (pintype "power_in"))
    )
    (net (code "77") (name "Net-(R32-Pad2)") (class "Default")
      (node (ref "R32") (pin "2") (pinfunction "2_2") (pintype "passive"))
      (node (ref "U3") (pin "6") (pinfunction "Sout_6") (pintype "power_in"))
    )
    (net (code "78") (name "Net-(R33-Pad2)") (class "Default")
      (node (ref "R33") (pin "2") (pinfunction "2_2") (pintype "passive"))
      (node (ref "U2") (pin "8") (pinfunction "Sout_8") (pintype "power_in"))
    )
    (net (code "79") (name "Net-(R34-Pad1)") (class "Default")
      (node (ref "R34") (pin "1") (pinfunction "1_1") (pintype "passive"))
      (node (ref "U2") (pin "9") (pinfunction "E_9") (pintype "power_in"))
    )
    (net (code "80") (name "Net-(R36-Pad1)") (class "Default")
      (node (ref "R36") (pin "1") (pinfunction "1_1") (pintype "passive"))
      (node (ref "U3") (pin "10") (pinfunction "C_10") (pintype "power_in"))
    )
    (net (code "81") (name "Net-(R37-Pad2)") (class "Default")
      (node (ref "R37") (pin "2") (pinfunction "2_2") (pintype "passive"))
      (node (ref "U4") (pin "6") (pinfunction "Sout_6") (pintype "power_in"))
    )
    (net (code "82") (name "Net-(R38-Pad1)") (class "Default")
      (node (ref "R38") (pin "1") (pinfunction "1_1") (pintype "passive"))
      (node (ref "U4") (pin "11") (pinfunction "E_11") (pintype "power_in"))
    )
    (net (code "83") (name "Net-(R40-Pad2)") (class "Default")
      (node (ref "R40") (pin "2") (pinfunction "2_2") (pintype "passive"))
      (node (ref "U3") (pin "8") (pinfunction "Sout_8") (pintype "power_in"))
    )
    (net (code "84") (name "Net-(R41-Pad2)") (class "Default")
      (node (ref "R41") (pin "2") (pinfunction "2_2") (pintype "passive"))
      (node (ref "U4") (pin "8") (pinfunction "Sout_8") (pintype "power_in"))
    )
    (net (code "85") (name "Net-(R42-Pad1)") (class "Default")
      (node (ref "R42") (pin "1") (pinfunction "1_1") (pintype "passive"))
      (node (ref "U4") (pin "9") (pinfunction "E_9") (pintype "power_in"))
    )
    (net (code "86") (name "PGND") (class "Default")
      (node (ref "1") (pin "2") (pinfunction "K_2") (pintype "passive"))
      (node (ref "2") (pin "2") (pinfunction "K_2") (pintype "passive"))
      (node (ref "C4") (pin "1") (pinfunction "1_1") (pintype "passive"))
      (node (ref "C5") (pin "2") (pinfunction "2_2") (pintype "passive"))
      (node (ref "P3") (pin "3") (pinfunction "3_3") (pintype "passive"))
      (node (ref "P4") (pin "3") (pinfunction "3_3") (pintype "passive"))
      (node (ref "P5") (pin "3") (pinfunction "3_3") (pintype "passive"))
      (node (ref "P6") (pin "3") (pinfunction "3_3") (pintype "passive"))
      (node (ref "POWER1") (pin "2") (pinfunction "2_2") (pintype "passive"))
      (node (ref "Q0") (pin "S") (pinfunction "S_S") (pintype "input"))
      (node (ref "Q1") (pin "S") (pinfunction "S_S") (pintype "input"))
      (node (ref "Q2") (pin "S") (pinfunction "S_S") (pintype "input"))
      (node (ref "Q3") (pin "S") (pinfunction "S_S") (pintype "input"))
      (node (ref "Q4") (pin "S") (pinfunction "S_S") (pintype "input"))
      (node (ref "Q5") (pin "S") (pinfunction "S_S") (pintype "input"))
      (node (ref "Q6") (pin "S") (pinfunction "S_S") (pintype "input"))
      (node (ref "Q7") (pin "S") (pinfunction "S_S") (pintype "input"))
      (node (ref "QS1") (pin "2") (pinfunction "E_2") (pintype "passive"))
      (node (ref "R14") (pin "1") (pinfunction "1_1") (pintype "passive"))
      (node (ref "R19") (pin "1") (pinfunction "1_1") (pintype "passive"))
      (node (ref "R23") (pin "1") (pinfunction "1_1") (pintype "passive"))
      (node (ref "R27") (pin "1") (pinfunction "1_1") (pintype "passive"))
      (node (ref "R31") (pin "1") (pinfunction "1_1") (pintype "passive"))
      (node (ref "R35") (pin "1") (pinfunction "1_1") (pintype "passive"))
      (node (ref "R39") (pin "1") (pinfunction "1_1") (pintype "passive"))
      (node (ref "R43") (pin "1") (pinfunction "1_1") (pintype "passive"))
      (node (ref "R48") (pin "2") (pinfunction "2_2") (pintype "passive"))
      (node (ref "hub1") (pin "2") (pinfunction "2_2") (pintype "passive"))
      (node (ref "hub1") (pin "4") (pinfunction "4_4") (pintype "passive"))
      (node (ref "hub1") (pin "6") (pinfunction "6_6") (pintype "passive"))
      (node (ref "hub2") (pin "2") (pinfunction "2_2") (pintype "passive"))
      (node (ref "hub2") (pin "4") (pinfunction "4_4") (pintype "passive"))
      (node (ref "hub2") (pin "6") (pinfunction "6_6") (pintype "passive"))
      (node (ref "step_down1") (pin "1") (pinfunction "GND_1") (pintype "passive"))
      (node (ref "step_down1") (pin "6") (pinfunction "GND_6") (pintype "passive"))
      (node (ref "step_down1") (pin "7") (pinfunction "GND_7") (pintype "passive"))
    )
    (net (code "87") (name "unconnected-(Core1-3V3-Pad14)") (class "Default")
      (node (ref "Core1") (pin "14") (pinfunction "3V3_14") (pintype "passive"))
    )
    (net (code "88") (name "unconnected-(Core1-NC-Pad3)") (class "Default")
      (node (ref "Core1") (pin "3") (pinfunction "NC_3") (pintype "passive"))
    )
    (net (code "89") (name "unconnected-(Core1-PA8-Pad42)") (class "Default")
      (node (ref "Core1") (pin "42") (pinfunction "PA8_42") (pintype "passive"))
    )
    (net (code "90") (name "unconnected-(Core1-PA9-Pad41)") (class "Default")
      (node (ref "Core1") (pin "41") (pinfunction "PA9_41") (pintype "passive"))
    )
    (net (code "91") (name "unconnected-(Core1-PA10-Pad40)") (class "Default")
      (node (ref "Core1") (pin "40") (pinfunction "PA10_40") (pintype "passive"))
    )
    (net (code "92") (name "unconnected-(Core1-PA13-Pad37)") (class "Default")
      (node (ref "Core1") (pin "37") (pinfunction "PA13_37") (pintype "passive"))
    )
    (net (code "93") (name "unconnected-(Core1-PA14-Pad36)") (class "Default")
      (node (ref "Core1") (pin "36") (pinfunction "PA14_36") (pintype "passive"))
    )
    (net (code "94") (name "unconnected-(Core1-PA15-Pad35)") (class "Default")
      (node (ref "Core1") (pin "35") (pinfunction "PA15_35") (pintype "passive"))
    )
    (net (code "95") (name "unconnected-(Core1-PB0-Pad21)") (class "Default")
      (node (ref "Core1") (pin "21") (pinfunction "PB0_21") (pintype "passive"))
    )
    (net (code "96") (name "unconnected-(Core1-PB1-Pad22)") (class "Default")
      (node (ref "Core1") (pin "22") (pinfunction "PB1_22") (pintype "passive"))
    )
    (net (code "97") (name "unconnected-(Core1-PB2-Pad23)") (class "Default")
      (node (ref "Core1") (pin "23") (pinfunction "PB2_23") (pintype "passive"))
    )
    (net (code "98") (name "unconnected-(Core1-PB3-Pad32)") (class "Default")
      (node (ref "Core1") (pin "32") (pinfunction "PB3_32") (pintype "passive"))
    )
    (net (code "99") (name "unconnected-(Core1-PB4-Pad31)") (class "Default")
      (node (ref "Core1") (pin "31") (pinfunction "PB4_31") (pintype "passive"))
    )
    (net (code "100") (name "unconnected-(Core1-PB5-Pad30)") (class "Default")
      (node (ref "Core1") (pin "30") (pinfunction "PB5_30") (pintype "passive"))
    )
    (net (code "101") (name "unconnected-(Core1-PB6-Pad29)") (class "Default")
      (node (ref "Core1") (pin "29") (pinfunction "PB6_29") (pintype "passive"))
    )
    (net (code "102") (name "unconnected-(Core1-PB7-Pad28)") (class "Default")
      (node (ref "Core1") (pin "28") (pinfunction "PB7_28") (pintype "passive"))
    )
    (net (code "103") (name "unconnected-(Core1-PB8-Pad27)") (class "Default")
      (node (ref "Core1") (pin "27") (pinfunction "PB8_27") (pintype "passive"))
    )
    (net (code "104") (name "unconnected-(Core1-PB9-Pad26)") (class "Default")
      (node (ref "Core1") (pin "26") (pinfunction "PB9_26") (pintype "passive"))
    )
    (net (code "105") (name "unconnected-(Core1-PC2-Pad8)") (class "Default")
      (node (ref "Core1") (pin "8") (pinfunction "PC2_8") (pintype "passive"))
    )
    (net (code "106") (name "unconnected-(Core1-PC3-Pad9)") (class "Default")
      (node (ref "Core1") (pin "9") (pinfunction "PC3_9") (pintype "passive"))
    )
    (net (code "107") (name "unconnected-(Core1-PC4-Pad19)") (class "Default")
      (node (ref "Core1") (pin "19") (pinfunction "PC4_19") (pintype "passive"))
    )
    (net (code "108") (name "unconnected-(Core1-PC5-Pad20)") (class "Default")
      (node (ref "Core1") (pin "20") (pinfunction "PC5_20") (pintype "passive"))
    )
    (net (code "109") (name "unconnected-(Core1-PC6-Pad46)") (class "Default")
      (node (ref "Core1") (pin "46") (pinfunction "PC6_46") (pintype "passive"))
    )
    (net (code "110") (name "unconnected-(Core1-PC7-Pad45)") (class "Default")
      (node (ref "Core1") (pin "45") (pinfunction "PC7_45") (pintype "passive"))
    )
    (net (code "111") (name "unconnected-(Core1-PC8-Pad44)") (class "Default")
      (node (ref "Core1") (pin "44") (pinfunction "PC8_44") (pintype "passive"))
    )
    (net (code "112") (name "unconnected-(Core1-PC9-Pad43)") (class "Default")
      (node (ref "Core1") (pin "43") (pinfunction "PC9_43") (pintype "passive"))
    )
    (net (code "113") (name "unconnected-(Core1-PC10-Pad34)") (class "Default")
      (node (ref "Core1") (pin "34") (pinfunction "PC10_34") (pintype "passive"))
    )
    (net (code "114") (name "unconnected-(Core1-PD2-Pad33)") (class "Default")
      (node (ref "Core1") (pin "33") (pinfunction "PD2_33") (pintype "passive"))
    )
    (net (code "115") (name "unconnected-(TJA1-Vref-Pad5)") (class "Default")
      (node (ref "TJA1") (pin "5") (pinfunction "Vref_5") (pintype "passive"))
    )
    (net (code "116") (name "unconnected-(step_down1-GND-Pad2)") (class "Default")
      (node (ref "step_down1") (pin "2") (pinfunction "GND_2") (pintype "passive"))
    )
    (net (code "117") (name "unconnected-(step_down1-NC-Pad3)") (class "Default")
      (node (ref "step_down1") (pin "3") (pinfunction "NC_3") (pintype "passive"))
    )
    (net (code "118") (name "unconnected-(step_down1-VIN-Pad4)") (class "Default")
      (node (ref "step_down1") (pin "4") (pinfunction "VIN_4") (pintype "passive"))
    )
    (net (code "119") (name "unconnected-(step_down1-VUP-Pad8)") (class "Default")
      (node (ref "step_down1") (pin "8") (pinfunction "VUP_8") (pintype "passive"))
    )
    (net (code "120") (name "unconnected-(step_down1-VUP-Pad9)") (class "Default")
      (node (ref "step_down1") (pin "9") (pinfunction "VUP_9") (pintype "passive"))
    )
  )
)
